# PT08.net
KiCad netlist of a schematic drawn in EAGLE
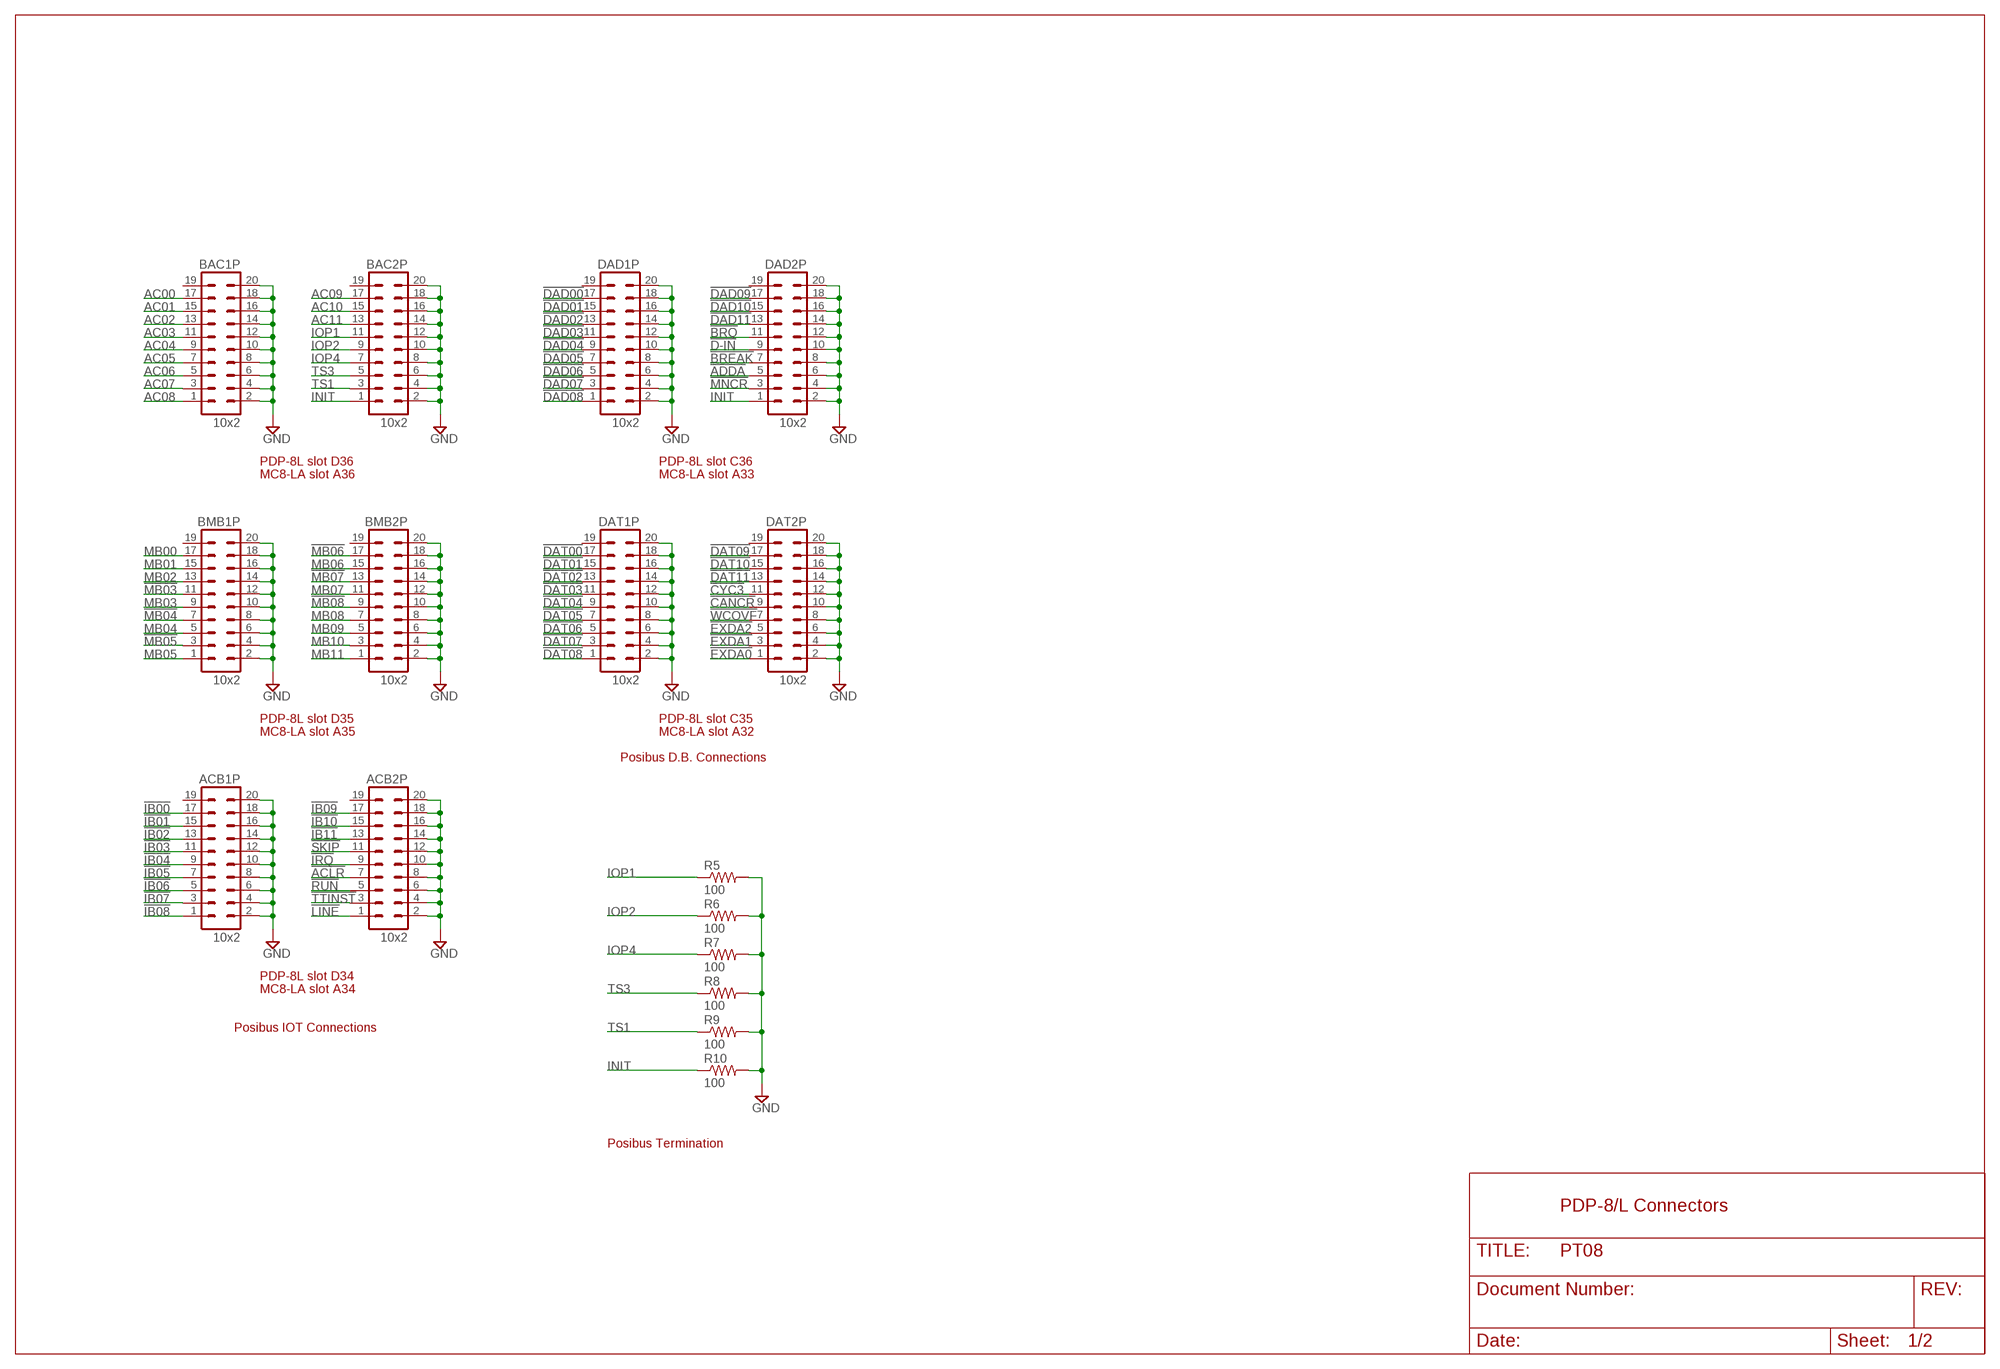
[diagram p0: schematic, sheet 1]
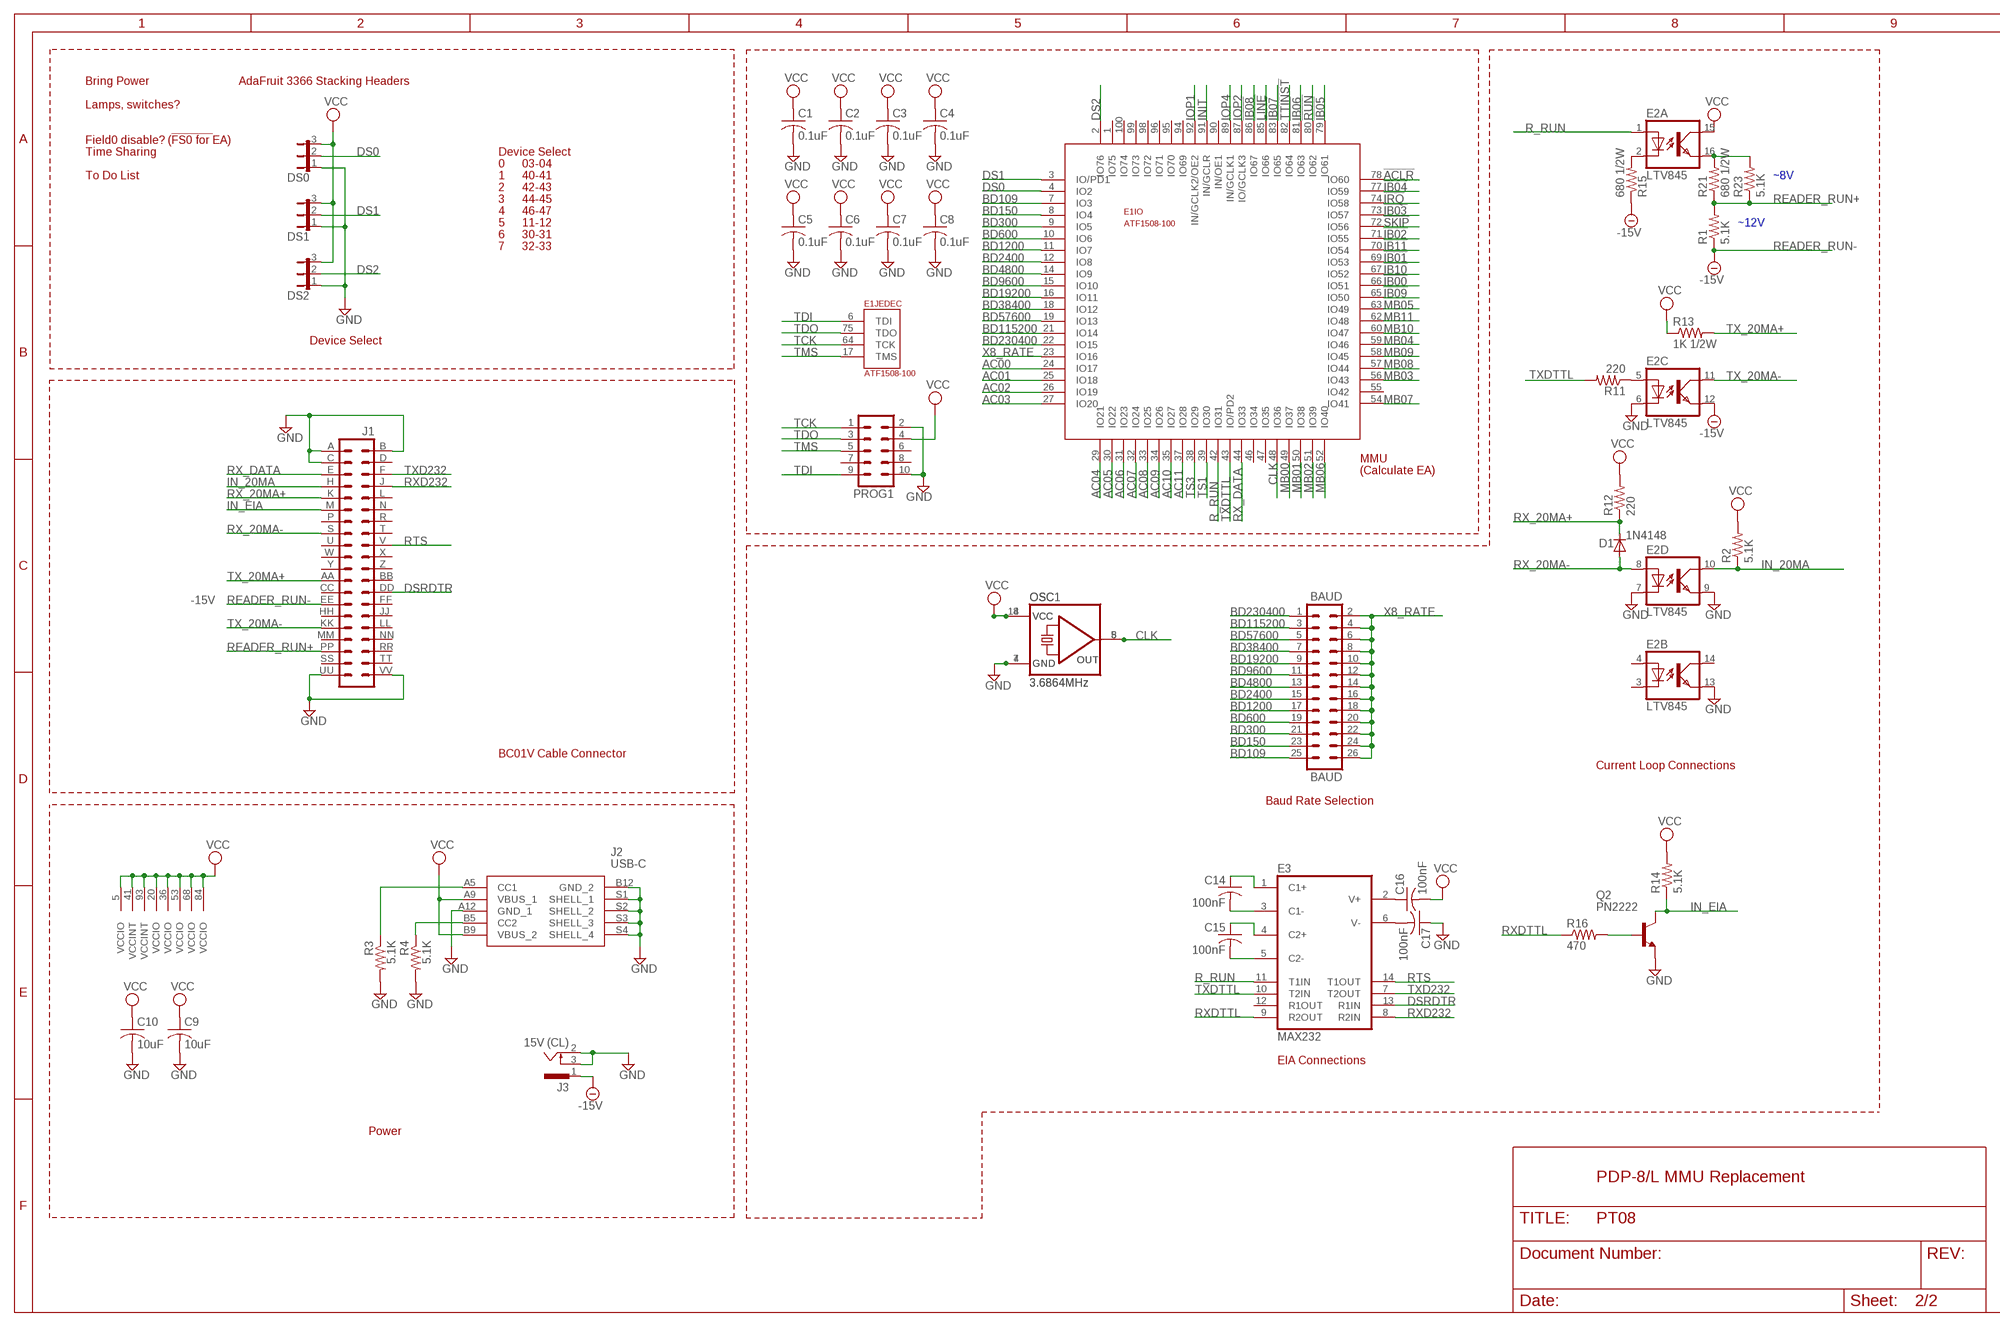
[diagram p1: schematic, sheet 2, part 1 of 2]
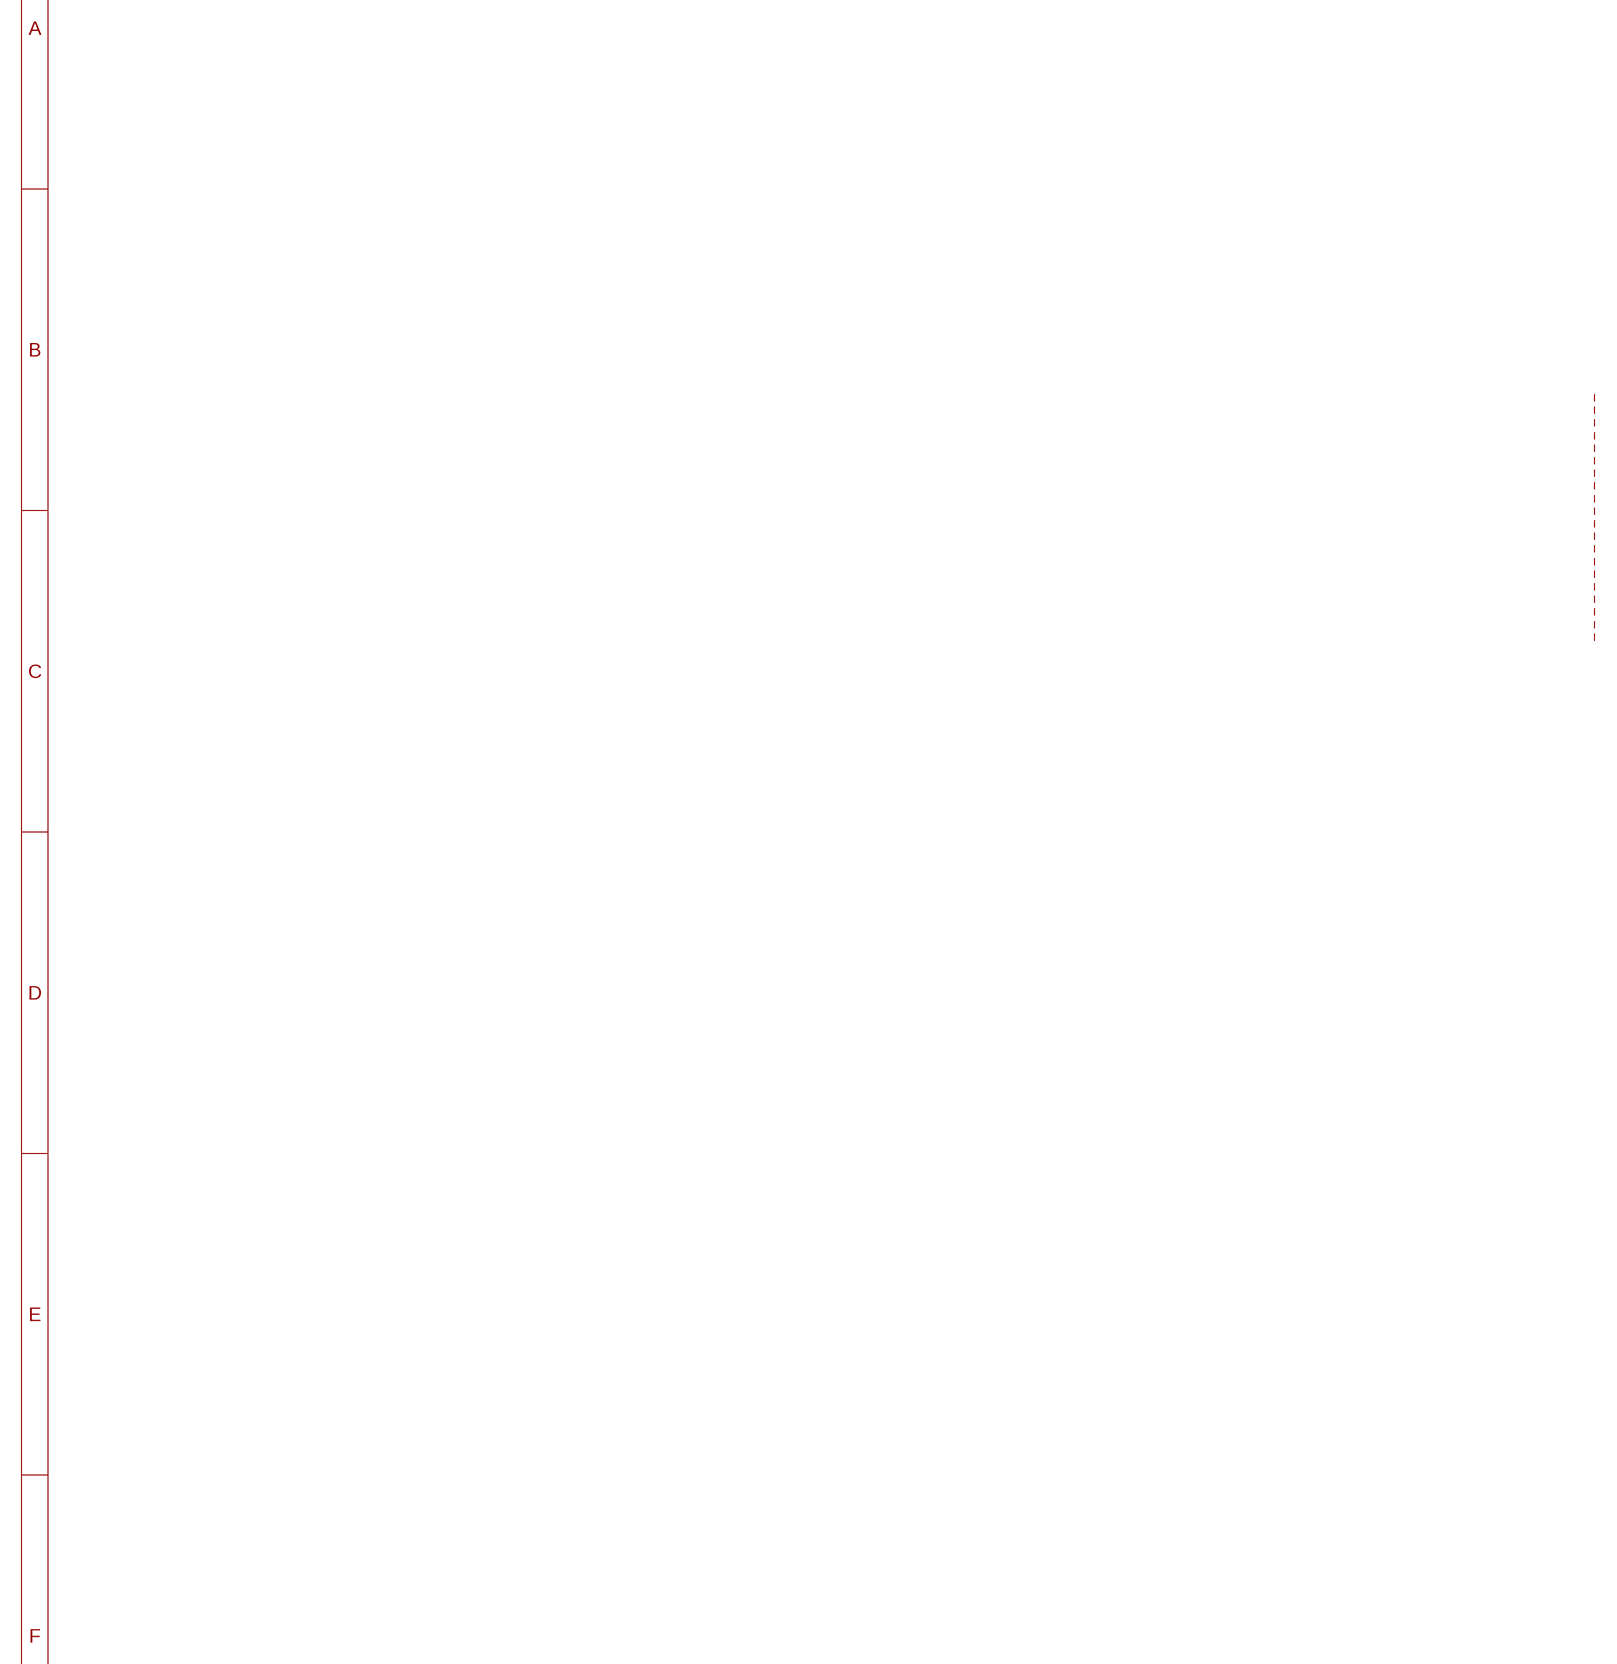
[diagram p2: schematic, sheet 2, part 2 of 2]

(export (version "E")
  (design (tool "Eeschema 10.0.6"))
  (components
    (comp (ref "BAUD")
      (value "BAUD")
      (footprint "eagle-import:MA13-2")
      (libsource (lib "eagle-import") (part "MA13-2"))
    )
    (comp (ref "C1")
      (value "0.1uF")
      (footprint "eagle-import:C0805")
      (libsource (lib "eagle-import") (part "C-USC0805"))
    )
    (comp (ref "C2")
      (value "0.1uF")
      (footprint "eagle-import:C0805")
      (libsource (lib "eagle-import") (part "C-USC0805"))
    )
    (comp (ref "C3")
      (value "0.1uF")
      (footprint "eagle-import:C0805")
      (libsource (lib "eagle-import") (part "C-USC0805"))
    )
    (comp (ref "C4")
      (value "0.1uF")
      (footprint "eagle-import:C0805")
      (libsource (lib "eagle-import") (part "C-USC0805"))
    )
    (comp (ref "C5")
      (value "0.1uF")
      (footprint "eagle-import:C0805")
      (libsource (lib "eagle-import") (part "C-USC0805"))
    )
    (comp (ref "C6")
      (value "0.1uF")
      (footprint "eagle-import:C0805")
      (libsource (lib "eagle-import") (part "C-USC0805"))
    )
    (comp (ref "C7")
      (value "0.1uF")
      (footprint "eagle-import:C0805")
      (libsource (lib "eagle-import") (part "C-USC0805"))
    )
    (comp (ref "C8")
      (value "0.1uF")
      (footprint "eagle-import:C0805")
      (libsource (lib "eagle-import") (part "C-USC0805"))
    )
    (comp (ref "C9")
      (value "10uF")
      (footprint "eagle-import:C0805")
      (libsource (lib "eagle-import") (part "C-USC0805"))
    )
    (comp (ref "C10")
      (value "10uF")
      (footprint "eagle-import:C0805")
      (libsource (lib "eagle-import") (part "C-USC0805"))
    )
    (comp (ref "C14")
      (value "100nF")
      (footprint "eagle-import:C0805")
      (libsource (lib "eagle-import") (part "C-USC0805"))
    )
    (comp (ref "C15")
      (value "100nF")
      (footprint "eagle-import:C0805")
      (libsource (lib "eagle-import") (part "C-USC0805"))
    )
    (comp (ref "C16")
      (value "100nF")
      (footprint "eagle-import:C0805")
      (libsource (lib "eagle-import") (part "C-USC0805"))
    )
    (comp (ref "C17")
      (value "100nF")
      (footprint "eagle-import:C0805")
      (libsource (lib "eagle-import") (part "C-USC0805"))
    )
    (comp (ref "D1")
      (value "1N4148")
      (footprint "eagle-import:SOD323-W")
      (libsource (lib "eagle-import") (part "DIODE-SOD323-W"))
    )
    (comp (ref "DS0")
      (value "JP2E")
      (footprint "eagle-import:JP2")
      (libsource (lib "eagle-import") (part "JP2E"))
    )
    (comp (ref "DS1")
      (value "JP2E")
      (footprint "eagle-import:JP2")
      (libsource (lib "eagle-import") (part "JP2E"))
    )
    (comp (ref "DS2")
      (value "JP2E")
      (footprint "eagle-import:JP2")
      (libsource (lib "eagle-import") (part "JP2E"))
    )
    (comp (ref "E1")
      (value "ATF1508-100")
      (footprint "eagle-import:PQFP-100")
      (libsource (lib "eagle-import") (part "ATF150X100PQFP"))
    )
    (comp (ref "E2")
      (value "LTV845")
      (footprint "eagle-import:DIL16")
      (fields (field (name "MF") "VISHAY/TELEFUNKEN") (field (name "MPN") "ILQ1"))
      (libsource (lib "eagle-import") (part "ILQ1"))
    )
    (comp (ref "E3")
      (value "MAX232")
      (footprint "eagle-import:DIL16")
      (fields (field (name "MF") "MAXIM") (field (name "MPN") "MAX232ACPE+"))
      (libsource (lib "eagle-import") (part "MAX232"))
    )
    (comp (ref "J1")
      (value "DEC40PINH")
      (footprint "eagle-import:DEC40PINH")
      (libsource (lib "eagle-import") (part "DEC40PINH"))
    )
    (comp (ref "J2")
      (value "USB-C")
      (footprint "eagle-import:USB497000A")
      (fields (field (name "MANUFACTURER_PART_NUMBER") "USB4970-00-A"))
      (libsource (lib "eagle-import") (part "USB4970-00-A"))
    )
    (comp (ref "J3")
      (value "15V (CL)")
      (footprint "eagle-import:SCD-014-A")
      (libsource (lib "eagle-import") (part "SCD-014A"))
    )
    (comp (ref "OSC")
      (value "3.6864MHz")
      (footprint "eagle-import:DIL08S")
      (libsource (lib "eagle-import") (part "QG5460"))
    )
    (comp (ref "OSC1")
      (value "3.6864MHz")
      (footprint "eagle-import:DIL14S")
      (libsource (lib "eagle-import") (part "QG5860"))
    )
    (comp (ref "PROG1")
      (value "ML10")
      (footprint "eagle-import:ML10")
      (libsource (lib "eagle-import") (part "ML10"))
    )
    (comp (ref "Q2")
      (value "PN2222")
      (footprint "eagle-import:SOT23-EBC")
      (libsource (lib "eagle-import") (part "-NPN-SOT23-EBC"))
    )
    (comp (ref "R1")
      (value "5.1K")
      (footprint "eagle-import:R0805")
      (libsource (lib "eagle-import") (part "R-US_R0805"))
    )
    (comp (ref "R2")
      (value "5.1K")
      (footprint "eagle-import:R0805")
      (libsource (lib "eagle-import") (part "R-US_R0805"))
    )
    (comp (ref "R3")
      (value "5.1K")
      (footprint "eagle-import:R0805")
      (libsource (lib "eagle-import") (part "R-US_R0805"))
    )
    (comp (ref "R4")
      (value "5.1K")
      (footprint "eagle-import:R0805")
      (libsource (lib "eagle-import") (part "R-US_R0805"))
    )
    (comp (ref "R11")
      (value "220")
      (footprint "eagle-import:R0805")
      (libsource (lib "eagle-import") (part "R-US_R0805"))
    )
    (comp (ref "R12")
      (value "220")
      (footprint "eagle-import:R0805")
      (libsource (lib "eagle-import") (part "R-US_R0805"))
    )
    (comp (ref "R13")
      (value "1K 1/2W")
      (footprint "eagle-import:0207_10")
      (libsource (lib "eagle-import") (part "R-US_0207/10"))
    )
    (comp (ref "R14")
      (value "5.1K")
      (footprint "eagle-import:R0805")
      (libsource (lib "eagle-import") (part "R-US_R0805"))
    )
    (comp (ref "R15")
      (value "680 1/2W")
      (footprint "eagle-import:0207_10")
      (libsource (lib "eagle-import") (part "R-US_0207/10"))
    )
    (comp (ref "R16")
      (value "470")
      (footprint "eagle-import:R0805")
      (libsource (lib "eagle-import") (part "R-US_R0805"))
    )
    (comp (ref "R21")
      (value "680 1/2W")
      (footprint "eagle-import:0207_10")
      (libsource (lib "eagle-import") (part "R-US_0207/10"))
    )
    (comp (ref "R23")
      (value "5.1K")
      (footprint "eagle-import:R0805")
      (libsource (lib "eagle-import") (part "R-US_R0805"))
    )
    (comp (ref "ACB1P")
      (value "10x2")
      (footprint "eagle-import:MA10-2")
      (libsource (lib "eagle-import") (part "MA10-2"))
    )
    (comp (ref "ACB2P")
      (value "10x2")
      (footprint "eagle-import:MA10-2")
      (libsource (lib "eagle-import") (part "MA10-2"))
    )
    (comp (ref "BAC1P")
      (value "10x2")
      (footprint "eagle-import:MA10-2")
      (libsource (lib "eagle-import") (part "MA10-2"))
    )
    (comp (ref "BAC2P")
      (value "10x2")
      (footprint "eagle-import:MA10-2")
      (libsource (lib "eagle-import") (part "MA10-2"))
    )
    (comp (ref "BMB1P")
      (value "10x2")
      (footprint "eagle-import:MA10-2")
      (libsource (lib "eagle-import") (part "MA10-2"))
    )
    (comp (ref "BMB2P")
      (value "10x2")
      (footprint "eagle-import:MA10-2")
      (libsource (lib "eagle-import") (part "MA10-2"))
    )
    (comp (ref "DAD1P")
      (value "10x2")
      (footprint "eagle-import:MA10-2")
      (libsource (lib "eagle-import") (part "MA10-2"))
    )
    (comp (ref "DAD2P")
      (value "10x2")
      (footprint "eagle-import:MA10-2")
      (libsource (lib "eagle-import") (part "MA10-2"))
    )
    (comp (ref "DAT1P")
      (value "10x2")
      (footprint "eagle-import:MA10-2")
      (libsource (lib "eagle-import") (part "MA10-2"))
    )
    (comp (ref "DAT2P")
      (value "10x2")
      (footprint "eagle-import:MA10-2")
      (libsource (lib "eagle-import") (part "MA10-2"))
    )
    (comp (ref "R5")
      (value "100")
      (footprint "eagle-import:R1206")
      (libsource (lib "eagle-import") (part "R-US_R1206"))
    )
    (comp (ref "R6")
      (value "100")
      (footprint "eagle-import:R1206")
      (libsource (lib "eagle-import") (part "R-US_R1206"))
    )
    (comp (ref "R7")
      (value "100")
      (footprint "eagle-import:R1206")
      (libsource (lib "eagle-import") (part "R-US_R1206"))
    )
    (comp (ref "R8")
      (value "100")
      (footprint "eagle-import:R1206")
      (libsource (lib "eagle-import") (part "R-US_R1206"))
    )
    (comp (ref "R9")
      (value "100")
      (footprint "eagle-import:R1206")
      (libsource (lib "eagle-import") (part "R-US_R1206"))
    )
    (comp (ref "R10")
      (value "100")
      (footprint "eagle-import:R1206")
      (libsource (lib "eagle-import") (part "R-US_R1206"))
    )
  )
  (nets
    (net (code "1") (name "-15V") (class "Default")
      (node (ref "E2") (pin "12") (pinfunction "EMIT_12") (pintype "passive"))
      (node (ref "J1") (pin "EE") (pinfunction "27_EE") (pintype "bidirectional"))
      (node (ref "J3") (pin "1") (pinfunction "1_1") (pintype "passive"))
      (node (ref "R1") (pin "1") (pinfunction "1_1") (pintype "passive"))
      (node (ref "R15") (pin "1") (pinfunction "1_1") (pintype "passive"))
    )
    (net (code "2") (name "AC00") (class "Default")
      (node (ref "BAC1P") (pin "17") (pinfunction "17_17") (pintype "passive"))
      (node (ref "E1") (pin "24") (pinfunction "IO17_24") (pintype "bidirectional"))
    )
    (net (code "3") (name "AC01") (class "Default")
      (node (ref "BAC1P") (pin "15") (pinfunction "15_15") (pintype "passive"))
      (node (ref "E1") (pin "25") (pinfunction "IO18_25") (pintype "bidirectional"))
    )
    (net (code "4") (name "AC02") (class "Default")
      (node (ref "BAC1P") (pin "13") (pinfunction "13_13") (pintype "passive"))
      (node (ref "E1") (pin "26") (pinfunction "IO19_26") (pintype "bidirectional"))
    )
    (net (code "5") (name "AC03") (class "Default")
      (node (ref "BAC1P") (pin "11") (pinfunction "11_11") (pintype "passive"))
      (node (ref "E1") (pin "27") (pinfunction "IO20_27") (pintype "bidirectional"))
    )
    (net (code "6") (name "AC04") (class "Default")
      (node (ref "BAC1P") (pin "9") (pinfunction "9_9") (pintype "passive"))
      (node (ref "E1") (pin "29") (pinfunction "IO21_29") (pintype "bidirectional"))
    )
    (net (code "7") (name "AC05") (class "Default")
      (node (ref "BAC1P") (pin "7") (pinfunction "7_7") (pintype "passive"))
      (node (ref "E1") (pin "30") (pinfunction "IO22_30") (pintype "bidirectional"))
    )
    (net (code "8") (name "AC06") (class "Default")
      (node (ref "BAC1P") (pin "5") (pinfunction "5_5") (pintype "passive"))
      (node (ref "E1") (pin "31") (pinfunction "IO23_31") (pintype "bidirectional"))
    )
    (net (code "9") (name "AC07") (class "Default")
      (node (ref "BAC1P") (pin "3") (pinfunction "3_3") (pintype "passive"))
      (node (ref "E1") (pin "32") (pinfunction "IO24_32") (pintype "bidirectional"))
    )
    (net (code "10") (name "AC08") (class "Default")
      (node (ref "BAC1P") (pin "1") (pinfunction "1_1") (pintype "passive"))
      (node (ref "E1") (pin "33") (pinfunction "IO25_33") (pintype "bidirectional"))
    )
    (net (code "11") (name "AC09") (class "Default")
      (node (ref "BAC2P") (pin "17") (pinfunction "17_17") (pintype "passive"))
      (node (ref "E1") (pin "34") (pinfunction "IO26_34") (pintype "bidirectional"))
    )
    (net (code "12") (name "AC10") (class "Default")
      (node (ref "BAC2P") (pin "15") (pinfunction "15_15") (pintype "passive"))
      (node (ref "E1") (pin "35") (pinfunction "IO27_35") (pintype "bidirectional"))
    )
    (net (code "13") (name "AC11") (class "Default")
      (node (ref "BAC2P") (pin "13") (pinfunction "13_13") (pintype "passive"))
      (node (ref "E1") (pin "37") (pinfunction "IO28_37") (pintype "bidirectional"))
    )
    (net (code "14") (name "BD109") (class "Default")
      (node (ref "BAUD") (pin "25") (pinfunction "25_25") (pintype "passive"))
      (node (ref "E1") (pin "7") (pinfunction "IO3_7") (pintype "bidirectional"))
    )
    (net (code "15") (name "BD150") (class "Default")
      (node (ref "BAUD") (pin "23") (pinfunction "23_23") (pintype "passive"))
      (node (ref "E1") (pin "8") (pinfunction "IO4_8") (pintype "bidirectional"))
    )
    (net (code "16") (name "BD300") (class "Default")
      (node (ref "BAUD") (pin "21") (pinfunction "21_21") (pintype "passive"))
      (node (ref "E1") (pin "9") (pinfunction "IO5_9") (pintype "bidirectional"))
    )
    (net (code "17") (name "BD600") (class "Default")
      (node (ref "BAUD") (pin "19") (pinfunction "19_19") (pintype "passive"))
      (node (ref "E1") (pin "10") (pinfunction "IO6_10") (pintype "bidirectional"))
    )
    (net (code "18") (name "BD1200") (class "Default")
      (node (ref "BAUD") (pin "17") (pinfunction "17_17") (pintype "passive"))
      (node (ref "E1") (pin "11") (pinfunction "IO7_11") (pintype "bidirectional"))
    )
    (net (code "19") (name "BD2400") (class "Default")
      (node (ref "BAUD") (pin "15") (pinfunction "15_15") (pintype "passive"))
      (node (ref "E1") (pin "12") (pinfunction "IO8_12") (pintype "bidirectional"))
    )
    (net (code "20") (name "BD4800") (class "Default")
      (node (ref "BAUD") (pin "13") (pinfunction "13_13") (pintype "passive"))
      (node (ref "E1") (pin "14") (pinfunction "IO9_14") (pintype "bidirectional"))
    )
    (net (code "21") (name "BD9600") (class "Default")
      (node (ref "BAUD") (pin "11") (pinfunction "11_11") (pintype "passive"))
      (node (ref "E1") (pin "15") (pinfunction "IO10_15") (pintype "bidirectional"))
    )
    (net (code "22") (name "BD19200") (class "Default")
      (node (ref "BAUD") (pin "9") (pinfunction "9_9") (pintype "passive"))
      (node (ref "E1") (pin "16") (pinfunction "IO11_16") (pintype "bidirectional"))
    )
    (net (code "23") (name "BD38400") (class "Default")
      (node (ref "BAUD") (pin "7") (pinfunction "7_7") (pintype "passive"))
      (node (ref "E1") (pin "18") (pinfunction "IO12_18") (pintype "bidirectional"))
    )
    (net (code "24") (name "BD57600") (class "Default")
      (node (ref "BAUD") (pin "5") (pinfunction "5_5") (pintype "passive"))
      (node (ref "E1") (pin "19") (pinfunction "IO13_19") (pintype "bidirectional"))
    )
    (net (code "25") (name "BD115200") (class "Default")
      (node (ref "BAUD") (pin "3") (pinfunction "3_3") (pintype "passive"))
      (node (ref "E1") (pin "21") (pinfunction "IO14_21") (pintype "bidirectional"))
    )
    (net (code "26") (name "BD230400") (class "Default")
      (node (ref "BAUD") (pin "1") (pinfunction "1_1") (pintype "passive"))
      (node (ref "E1") (pin "22") (pinfunction "IO15_22") (pintype "bidirectional"))
    )
    (net (code "27") (name "CLK") (class "Default")
      (node (ref "E1") (pin "48") (pinfunction "IO36_48") (pintype "bidirectional"))
      (node (ref "OSC") (pin "5") (pinfunction "OUT_5") (pintype "output"))
      (node (ref "OSC1") (pin "8") (pinfunction "OUT_8") (pintype "output"))
    )
    (net (code "28") (name "DS0") (class "Default")
      (node (ref "DS0") (pin "2") (pinfunction "2_2") (pintype "passive"))
      (node (ref "E1") (pin "4") (pinfunction "IO2_4") (pintype "bidirectional"))
    )
    (net (code "29") (name "DS1") (class "Default")
      (node (ref "DS1") (pin "2") (pinfunction "2_2") (pintype "passive"))
      (node (ref "E1") (pin "3") (pinfunction "IO/PD1_3") (pintype "bidirectional"))
    )
    (net (code "30") (name "DS2") (class "Default")
      (node (ref "DS2") (pin "2") (pinfunction "2_2") (pintype "passive"))
      (node (ref "E1") (pin "2") (pinfunction "IO76_2") (pintype "bidirectional"))
    )
    (net (code "31") (name "DSRDTR") (class "Default")
      (node (ref "E3") (pin "13") (pinfunction "R1IN_13") (pintype "input"))
      (node (ref "J1") (pin "DD") (pinfunction "26_DD") (pintype "bidirectional"))
    )
    (net (code "32") (name "GND") (class "Default")
      (node (ref "ACB1P") (pin "10") (pinfunction "10_10") (pintype "passive"))
      (node (ref "ACB1P") (pin "12") (pinfunction "12_12") (pintype "passive"))
      (node (ref "ACB1P") (pin "14") (pinfunction "14_14") (pintype "passive"))
      (node (ref "ACB1P") (pin "16") (pinfunction "16_16") (pintype "passive"))
      (node (ref "ACB1P") (pin "18") (pinfunction "18_18") (pintype "passive"))
      (node (ref "ACB1P") (pin "2") (pinfunction "2_2") (pintype "passive"))
      (node (ref "ACB1P") (pin "20") (pinfunction "20_20") (pintype "passive"))
      (node (ref "ACB1P") (pin "4") (pinfunction "4_4") (pintype "passive"))
      (node (ref "ACB1P") (pin "6") (pinfunction "6_6") (pintype "passive"))
      (node (ref "ACB1P") (pin "8") (pinfunction "8_8") (pintype "passive"))
      (node (ref "ACB2P") (pin "10") (pinfunction "10_10") (pintype "passive"))
      (node (ref "ACB2P") (pin "12") (pinfunction "12_12") (pintype "passive"))
      (node (ref "ACB2P") (pin "14") (pinfunction "14_14") (pintype "passive"))
      (node (ref "ACB2P") (pin "16") (pinfunction "16_16") (pintype "passive"))
      (node (ref "ACB2P") (pin "18") (pinfunction "18_18") (pintype "passive"))
      (node (ref "ACB2P") (pin "2") (pinfunction "2_2") (pintype "passive"))
      (node (ref "ACB2P") (pin "20") (pinfunction "20_20") (pintype "passive"))
      (node (ref "ACB2P") (pin "4") (pinfunction "4_4") (pintype "passive"))
      (node (ref "ACB2P") (pin "6") (pinfunction "6_6") (pintype "passive"))
      (node (ref "ACB2P") (pin "8") (pinfunction "8_8") (pintype "passive"))
      (node (ref "BAC1P") (pin "10") (pinfunction "10_10") (pintype "passive"))
      (node (ref "BAC1P") (pin "12") (pinfunction "12_12") (pintype "passive"))
      (node (ref "BAC1P") (pin "14") (pinfunction "14_14") (pintype "passive"))
      (node (ref "BAC1P") (pin "16") (pinfunction "16_16") (pintype "passive"))
      (node (ref "BAC1P") (pin "18") (pinfunction "18_18") (pintype "passive"))
      (node (ref "BAC1P") (pin "2") (pinfunction "2_2") (pintype "passive"))
      (node (ref "BAC1P") (pin "20") (pinfunction "20_20") (pintype "passive"))
      (node (ref "BAC1P") (pin "4") (pinfunction "4_4") (pintype "passive"))
      (node (ref "BAC1P") (pin "6") (pinfunction "6_6") (pintype "passive"))
      (node (ref "BAC1P") (pin "8") (pinfunction "8_8") (pintype "passive"))
      (node (ref "BAC2P") (pin "10") (pinfunction "10_10") (pintype "passive"))
      (node (ref "BAC2P") (pin "12") (pinfunction "12_12") (pintype "passive"))
      (node (ref "BAC2P") (pin "14") (pinfunction "14_14") (pintype "passive"))
      (node (ref "BAC2P") (pin "16") (pinfunction "16_16") (pintype "passive"))
      (node (ref "BAC2P") (pin "18") (pinfunction "18_18") (pintype "passive"))
      (node (ref "BAC2P") (pin "2") (pinfunction "2_2") (pintype "passive"))
      (node (ref "BAC2P") (pin "20") (pinfunction "20_20") (pintype "passive"))
      (node (ref "BAC2P") (pin "4") (pinfunction "4_4") (pintype "passive"))
      (node (ref "BAC2P") (pin "6") (pinfunction "6_6") (pintype "passive"))
      (node (ref "BAC2P") (pin "8") (pinfunction "8_8") (pintype "passive"))
      (node (ref "BMB1P") (pin "10") (pinfunction "10_10") (pintype "passive"))
      (node (ref "BMB1P") (pin "12") (pinfunction "12_12") (pintype "passive"))
      (node (ref "BMB1P") (pin "14") (pinfunction "14_14") (pintype "passive"))
      (node (ref "BMB1P") (pin "16") (pinfunction "16_16") (pintype "passive"))
      (node (ref "BMB1P") (pin "18") (pinfunction "18_18") (pintype "passive"))
      (node (ref "BMB1P") (pin "2") (pinfunction "2_2") (pintype "passive"))
      (node (ref "BMB1P") (pin "20") (pinfunction "20_20") (pintype "passive"))
      (node (ref "BMB1P") (pin "4") (pinfunction "4_4") (pintype "passive"))
      (node (ref "BMB1P") (pin "6") (pinfunction "6_6") (pintype "passive"))
      (node (ref "BMB1P") (pin "8") (pinfunction "8_8") (pintype "passive"))
      (node (ref "BMB2P") (pin "10") (pinfunction "10_10") (pintype "passive"))
      (node (ref "BMB2P") (pin "12") (pinfunction "12_12") (pintype "passive"))
      (node (ref "BMB2P") (pin "14") (pinfunction "14_14") (pintype "passive"))
      (node (ref "BMB2P") (pin "16") (pinfunction "16_16") (pintype "passive"))
      (node (ref "BMB2P") (pin "18") (pinfunction "18_18") (pintype "passive"))
      (node (ref "BMB2P") (pin "2") (pinfunction "2_2") (pintype "passive"))
      (node (ref "BMB2P") (pin "20") (pinfunction "20_20") (pintype "passive"))
      (node (ref "BMB2P") (pin "4") (pinfunction "4_4") (pintype "passive"))
      (node (ref "BMB2P") (pin "6") (pinfunction "6_6") (pintype "passive"))
      (node (ref "BMB2P") (pin "8") (pinfunction "8_8") (pintype "passive"))
      (node (ref "C1") (pin "2") (pinfunction "2_2") (pintype "passive"))
      (node (ref "C10") (pin "2") (pinfunction "2_2") (pintype "passive"))
      (node (ref "C17") (pin "1") (pinfunction "1_1") (pintype "passive"))
      (node (ref "C2") (pin "2") (pinfunction "2_2") (pintype "passive"))
      (node (ref "C3") (pin "2") (pinfunction "2_2") (pintype "passive"))
      (node (ref "C4") (pin "2") (pinfunction "2_2") (pintype "passive"))
      (node (ref "C5") (pin "2") (pinfunction "2_2") (pintype "passive"))
      (node (ref "C6") (pin "2") (pinfunction "2_2") (pintype "passive"))
      (node (ref "C7") (pin "2") (pinfunction "2_2") (pintype "passive"))
      (node (ref "C8") (pin "2") (pinfunction "2_2") (pintype "passive"))
      (node (ref "C9") (pin "2") (pinfunction "2_2") (pintype "passive"))
      (node (ref "DAD1P") (pin "10") (pinfunction "10_10") (pintype "passive"))
      (node (ref "DAD1P") (pin "12") (pinfunction "12_12") (pintype "passive"))
      (node (ref "DAD1P") (pin "14") (pinfunction "14_14") (pintype "passive"))
      (node (ref "DAD1P") (pin "16") (pinfunction "16_16") (pintype "passive"))
      (node (ref "DAD1P") (pin "18") (pinfunction "18_18") (pintype "passive"))
      (node (ref "DAD1P") (pin "2") (pinfunction "2_2") (pintype "passive"))
      (node (ref "DAD1P") (pin "20") (pinfunction "20_20") (pintype "passive"))
      (node (ref "DAD1P") (pin "4") (pinfunction "4_4") (pintype "passive"))
      (node (ref "DAD1P") (pin "6") (pinfunction "6_6") (pintype "passive"))
      (node (ref "DAD1P") (pin "8") (pinfunction "8_8") (pintype "passive"))
      (node (ref "DAD2P") (pin "10") (pinfunction "10_10") (pintype "passive"))
      (node (ref "DAD2P") (pin "12") (pinfunction "12_12") (pintype "passive"))
      (node (ref "DAD2P") (pin "14") (pinfunction "14_14") (pintype "passive"))
      (node (ref "DAD2P") (pin "16") (pinfunction "16_16") (pintype "passive"))
      (node (ref "DAD2P") (pin "18") (pinfunction "18_18") (pintype "passive"))
      (node (ref "DAD2P") (pin "2") (pinfunction "2_2") (pintype "passive"))
      (node (ref "DAD2P") (pin "20") (pinfunction "20_20") (pintype "passive"))
      (node (ref "DAD2P") (pin "4") (pinfunction "4_4") (pintype "passive"))
      (node (ref "DAD2P") (pin "6") (pinfunction "6_6") (pintype "passive"))
      (node (ref "DAD2P") (pin "8") (pinfunction "8_8") (pintype "passive"))
      (node (ref "DAT1P") (pin "10") (pinfunction "10_10") (pintype "passive"))
      (node (ref "DAT1P") (pin "12") (pinfunction "12_12") (pintype "passive"))
      (node (ref "DAT1P") (pin "14") (pinfunction "14_14") (pintype "passive"))
      (node (ref "DAT1P") (pin "16") (pinfunction "16_16") (pintype "passive"))
      (node (ref "DAT1P") (pin "18") (pinfunction "18_18") (pintype "passive"))
      (node (ref "DAT1P") (pin "2") (pinfunction "2_2") (pintype "passive"))
      (node (ref "DAT1P") (pin "20") (pinfunction "20_20") (pintype "passive"))
      (node (ref "DAT1P") (pin "4") (pinfunction "4_4") (pintype "passive"))
      (node (ref "DAT1P") (pin "6") (pinfunction "6_6") (pintype "passive"))
      (node (ref "DAT1P") (pin "8") (pinfunction "8_8") (pintype "passive"))
      (node (ref "DAT2P") (pin "10") (pinfunction "10_10") (pintype "passive"))
      (node (ref "DAT2P") (pin "12") (pinfunction "12_12") (pintype "passive"))
      (node (ref "DAT2P") (pin "14") (pinfunction "14_14") (pintype "passive"))
      (node (ref "DAT2P") (pin "16") (pinfunction "16_16") (pintype "passive"))
      (node (ref "DAT2P") (pin "18") (pinfunction "18_18") (pintype "passive"))
      (node (ref "DAT2P") (pin "2") (pinfunction "2_2") (pintype "passive"))
      (node (ref "DAT2P") (pin "20") (pinfunction "20_20") (pintype "passive"))
      (node (ref "DAT2P") (pin "4") (pinfunction "4_4") (pintype "passive"))
      (node (ref "DAT2P") (pin "6") (pinfunction "6_6") (pintype "passive"))
      (node (ref "DAT2P") (pin "8") (pinfunction "8_8") (pintype "passive"))
      (node (ref "DS0") (pin "1") (pinfunction "1_1") (pintype "passive"))
      (node (ref "DS1") (pin "1") (pinfunction "1_1") (pintype "passive"))
      (node (ref "DS2") (pin "1") (pinfunction "1_1") (pintype "passive"))
      (node (ref "E2") (pin "13") (pinfunction "EMIT_13") (pintype "passive"))
      (node (ref "E2") (pin "6") (pinfunction "C_6") (pintype "passive"))
      (node (ref "E2") (pin "7") (pinfunction "C_7") (pintype "passive"))
      (node (ref "E2") (pin "9") (pinfunction "EMIT_9") (pintype "passive"))
      (node (ref "J1") (pin "A") (pinfunction "1_A") (pintype "bidirectional"))
      (node (ref "J1") (pin "B") (pinfunction "2_B") (pintype "bidirectional"))
      (node (ref "J1") (pin "C") (pinfunction "3_C") (pintype "bidirectional"))
      (node (ref "J1") (pin "UU") (pinfunction "39_UU") (pintype "bidirectional"))
      (node (ref "J1") (pin "VV") (pinfunction "40_VV") (pintype "bidirectional"))
      (node (ref "J2") (pin "A12") (pinfunction "GND_1_A12") (pintype "bidirectional"))
      (node (ref "J2") (pin "B12") (pinfunction "GND_2_B12") (pintype "bidirectional"))
      (node (ref "J2") (pin "S1") (pinfunction "SHELL_1_S1") (pintype "bidirectional"))
      (node (ref "J2") (pin "S2") (pinfunction "SHELL_2_S2") (pintype "bidirectional"))
      (node (ref "J2") (pin "S3") (pinfunction "SHELL_3_S3") (pintype "bidirectional"))
      (node (ref "J2") (pin "S4") (pinfunction "SHELL_4_S4") (pintype "bidirectional"))
      (node (ref "J3") (pin "2") (pinfunction "2_2") (pintype "passive"))
      (node (ref "J3") (pin "3") (pinfunction "3_3") (pintype "passive"))
      (node (ref "OSC") (pin "4") (pinfunction "GND_4") (pintype "power_in"))
      (node (ref "OSC1") (pin "7") (pinfunction "GND_7") (pintype "power_in"))
      (node (ref "PROG1") (pin "10") (pinfunction "10_10") (pintype "passive"))
      (node (ref "PROG1") (pin "2") (pinfunction "2_2") (pintype "passive"))
      (node (ref "Q2") (pin "E") (pinfunction "E_E") (pintype "passive"))
      (node (ref "R10") (pin "2") (pinfunction "2_2") (pintype "passive"))
      (node (ref "R3") (pin "2") (pinfunction "2_2") (pintype "passive"))
      (node (ref "R4") (pin "2") (pinfunction "2_2") (pintype "passive"))
      (node (ref "R5") (pin "2") (pinfunction "2_2") (pintype "passive"))
      (node (ref "R6") (pin "2") (pinfunction "2_2") (pintype "passive"))
      (node (ref "R7") (pin "2") (pinfunction "2_2") (pintype "passive"))
      (node (ref "R8") (pin "2") (pinfunction "2_2") (pintype "passive"))
      (node (ref "R9") (pin "2") (pinfunction "2_2") (pintype "passive"))
    )
    (net (code "33") (name "INIT") (class "Default")
      (node (ref "BAC2P") (pin "1") (pinfunction "1_1") (pintype "passive"))
      (node (ref "DAD2P") (pin "1") (pinfunction "1_1") (pintype "passive"))
      (node (ref "E1") (pin "91") (pinfunction "IN/GCLR_91") (pintype "input"))
      (node (ref "R10") (pin "1") (pinfunction "1_1") (pintype "passive"))
    )
    (net (code "34") (name "IN_20MA") (class "Default")
      (node (ref "E2") (pin "10") (pinfunction "COL_10") (pintype "passive"))
      (node (ref "J1") (pin "H") (pinfunction "7_H") (pintype "bidirectional"))
      (node (ref "R2") (pin "1") (pinfunction "1_1") (pintype "passive"))
    )
    (net (code "35") (name "IN_EIA") (class "Default")
      (node (ref "J1") (pin "M") (pinfunction "11_M") (pintype "bidirectional"))
      (node (ref "Q2") (pin "C") (pinfunction "C_C") (pintype "passive"))
      (node (ref "R14") (pin "1") (pinfunction "1_1") (pintype "passive"))
    )
    (net (code "36") (name "IOP1") (class "Default")
      (node (ref "BAC2P") (pin "11") (pinfunction "11_11") (pintype "passive"))
      (node (ref "E1") (pin "92") (pinfunction "IN/GCLK2/OE2_92") (pintype "input"))
      (node (ref "R5") (pin "1") (pinfunction "1_1") (pintype "passive"))
    )
    (net (code "37") (name "IOP2") (class "Default")
      (node (ref "BAC2P") (pin "9") (pinfunction "9_9") (pintype "passive"))
      (node (ref "E1") (pin "87") (pinfunction "IO/GCLK3_87") (pintype "bidirectional"))
      (node (ref "R6") (pin "1") (pinfunction "1_1") (pintype "passive"))
    )
    (net (code "38") (name "IOP4") (class "Default")
      (node (ref "BAC2P") (pin "7") (pinfunction "7_7") (pintype "passive"))
      (node (ref "E1") (pin "89") (pinfunction "IN/GCLK1_89") (pintype "input"))
      (node (ref "R7") (pin "1") (pinfunction "1_1") (pintype "passive"))
    )
    (net (code "39") (name "MB00") (class "Default")
      (node (ref "BMB1P") (pin "17") (pinfunction "17_17") (pintype "passive"))
      (node (ref "E1") (pin "49") (pinfunction "IO37_49") (pintype "bidirectional"))
    )
    (net (code "40") (name "MB01") (class "Default")
      (node (ref "BMB1P") (pin "15") (pinfunction "15_15") (pintype "passive"))
      (node (ref "E1") (pin "50") (pinfunction "IO38_50") (pintype "bidirectional"))
    )
    (net (code "41") (name "MB02") (class "Default")
      (node (ref "BMB1P") (pin "13") (pinfunction "13_13") (pintype "passive"))
      (node (ref "E1") (pin "51") (pinfunction "IO39_51") (pintype "bidirectional"))
    )
    (net (code "42") (name "MB03") (class "Default")
      (node (ref "BMB1P") (pin "9") (pinfunction "9_9") (pintype "passive"))
      (node (ref "E1") (pin "56") (pinfunction "IO43_56") (pintype "bidirectional"))
    )
    (net (code "43") (name "MB04") (class "Default")
      (node (ref "BMB1P") (pin "5") (pinfunction "5_5") (pintype "passive"))
      (node (ref "E1") (pin "59") (pinfunction "IO46_59") (pintype "bidirectional"))
    )
    (net (code "44") (name "MB05") (class "Default")
      (node (ref "BMB1P") (pin "1") (pinfunction "1_1") (pintype "passive"))
      (node (ref "E1") (pin "63") (pinfunction "IO49_63") (pintype "bidirectional"))
    )
    (net (code "45") (name "MB06") (class "Default")
      (node (ref "BMB2P") (pin "15") (pinfunction "15_15") (pintype "passive"))
      (node (ref "E1") (pin "52") (pinfunction "IO40_52") (pintype "bidirectional"))
    )
    (net (code "46") (name "MB07") (class "Default")
      (node (ref "BMB2P") (pin "11") (pinfunction "11_11") (pintype "passive"))
      (node (ref "E1") (pin "54") (pinfunction "IO41_54") (pintype "bidirectional"))
    )
    (net (code "47") (name "MB08") (class "Default")
      (node (ref "BMB2P") (pin "7") (pinfunction "7_7") (pintype "passive"))
      (node (ref "E1") (pin "57") (pinfunction "IO44_57") (pintype "bidirectional"))
    )
    (net (code "48") (name "MB09") (class "Default")
      (node (ref "BMB2P") (pin "5") (pinfunction "5_5") (pintype "passive"))
      (node (ref "E1") (pin "58") (pinfunction "IO45_58") (pintype "bidirectional"))
    )
    (net (code "49") (name "MB10") (class "Default")
      (node (ref "BMB2P") (pin "3") (pinfunction "3_3") (pintype "passive"))
      (node (ref "E1") (pin "60") (pinfunction "IO47_60") (pintype "bidirectional"))
    )
    (net (code "50") (name "MB11") (class "Default")
      (node (ref "BMB2P") (pin "1") (pinfunction "1_1") (pintype "passive"))
      (node (ref "E1") (pin "62") (pinfunction "IO48_62") (pintype "bidirectional"))
    )
    (net (code "51") (name "Net-(E2A-C)") (class "Default")
      (node (ref "E2") (pin "2") (pinfunction "C_2") (pintype "passive"))
      (node (ref "R15") (pin "2") (pinfunction "2_2") (pintype "passive"))
    )
    (net (code "52") (name "Net-(E2A-EMIT)") (class "Default")
      (node (ref "E2") (pin "16") (pinfunction "EMIT_16") (pintype "passive"))
      (node (ref "R21") (pin "2") (pinfunction "2_2") (pintype "passive"))
      (node (ref "R23") (pin "2") (pinfunction "2_2") (pintype "passive"))
    )
    (net (code "53") (name "Net-(E2C-A)") (class "Default")
      (node (ref "E2") (pin "5") (pinfunction "A_5") (pintype "passive"))
      (node (ref "R11") (pin "1") (pinfunction "1_1") (pintype "passive"))
    )
    (net (code "54") (name "Net-(E3A-C1+)") (class "Default")
      (node (ref "C14") (pin "1") (pinfunction "1_1") (pintype "passive"))
      (node (ref "E3") (pin "1") (pinfunction "C1+_1") (pintype "bidirectional"))
    )
    (net (code "55") (name "Net-(E3A-C1-)") (class "Default")
      (node (ref "C14") (pin "2") (pinfunction "2_2") (pintype "passive"))
      (node (ref "E3") (pin "3") (pinfunction "C1-_3") (pintype "bidirectional"))
    )
    (net (code "56") (name "Net-(E3A-C2+)") (class "Default")
      (node (ref "C15") (pin "1") (pinfunction "1_1") (pintype "passive"))
      (node (ref "E3") (pin "4") (pinfunction "C2+_4") (pintype "bidirectional"))
    )
    (net (code "57") (name "Net-(E3A-C2-)") (class "Default")
      (node (ref "C15") (pin "2") (pinfunction "2_2") (pintype "passive"))
      (node (ref "E3") (pin "5") (pinfunction "C2-_5") (pintype "bidirectional"))
    )
    (net (code "58") (name "Net-(E3A-V+)") (class "Default")
      (node (ref "C16") (pin "1") (pinfunction "1_1") (pintype "passive"))
      (node (ref "E3") (pin "2") (pinfunction "V+_2") (pintype "bidirectional"))
    )
    (net (code "59") (name "Net-(E3A-V-)") (class "Default")
      (node (ref "C17") (pin "2") (pinfunction "2_2") (pintype "passive"))
      (node (ref "E3") (pin "6") (pinfunction "V-_6") (pintype "bidirectional"))
    )
    (net (code "60") (name "Net-(J2-CC1)") (class "Default")
      (node (ref "J2") (pin "A5") (pinfunction "CC1_A5") (pintype "bidirectional"))
      (node (ref "R3") (pin "1") (pinfunction "1_1") (pintype "passive"))
    )
    (net (code "61") (name "Net-(J2-CC2)") (class "Default")
      (node (ref "J2") (pin "B5") (pinfunction "CC2_B5") (pintype "bidirectional"))
      (node (ref "R4") (pin "1") (pinfunction "1_1") (pintype "passive"))
    )
    (net (code "62") (name "Net-(Q2-PadB)") (class "Default")
      (node (ref "Q2") (pin "B") (pinfunction "B_B") (pintype "passive"))
      (node (ref "R16") (pin "2") (pinfunction "2_2") (pintype "passive"))
    )
    (net (code "63") (name "READER_RUN+") (class "Default")
      (node (ref "J1") (pin "PP") (pinfunction "35_PP") (pintype "bidirectional"))
      (node (ref "R1") (pin "2") (pinfunction "2_2") (pintype "passive"))
      (node (ref "R21") (pin "1") (pinfunction "1_1") (pintype "passive"))
      (node (ref "R23") (pin "1") (pinfunction "1_1") (pintype "passive"))
    )
    (net (code "64") (name "RTS") (class "Default")
      (node (ref "E3") (pin "14") (pinfunction "T1OUT_14") (pintype "output"))
      (node (ref "J1") (pin "V") (pinfunction "18_V") (pintype "bidirectional"))
    )
    (net (code "65") (name "RXD232") (class "Default")
      (node (ref "E3") (pin "8") (pinfunction "R2IN_8") (pintype "input"))
      (node (ref "J1") (pin "J") (pinfunction "8_J") (pintype "bidirectional"))
    )
    (net (code "66") (name "RXDTTL") (class "Default")
      (node (ref "E3") (pin "9") (pinfunction "R2OUT_9") (pintype "output"))
      (node (ref "R16") (pin "1") (pinfunction "1_1") (pintype "passive"))
    )
    (net (code "67") (name "RX_20MA+") (class "Default")
      (node (ref "D1") (pin "C") (pinfunction "C_C") (pintype "passive"))
      (node (ref "J1") (pin "K") (pinfunction "9_K") (pintype "bidirectional"))
      (node (ref "R12") (pin "1") (pinfunction "1_1") (pintype "passive"))
    )
    (net (code "68") (name "RX_20MA-") (class "Default")
      (node (ref "D1") (pin "A") (pinfunction "A_A") (pintype "passive"))
      (node (ref "E2") (pin "8") (pinfunction "A_8") (pintype "passive"))
      (node (ref "J1") (pin "S") (pinfunction "15_S") (pintype "bidirectional"))
    )
    (net (code "69") (name "RX_DATA") (class "Default")
      (node (ref "E1") (pin "44") (pinfunction "IO33_44") (pintype "bidirectional"))
      (node (ref "J1") (pin "E") (pinfunction "5_E") (pintype "bidirectional"))
    )
    (net (code "70") (name "R_RUN") (class "Default")
      (node (ref "E1") (pin "42") (pinfunction "IO31_42") (pintype "bidirectional"))
      (node (ref "E2") (pin "1") (pinfunction "A_1") (pintype "passive"))
      (node (ref "E3") (pin "11") (pinfunction "T1IN_11") (pintype "input"))
    )
    (net (code "71") (name "TCK") (class "Default")
      (node (ref "E1") (pin "64") (pinfunction "TCK_64") (pintype "bidirectional"))
      (node (ref "PROG1") (pin "1") (pinfunction "1_1") (pintype "passive"))
    )
    (net (code "72") (name "TDI") (class "Default")
      (node (ref "E1") (pin "6") (pinfunction "TDI_6") (pintype "bidirectional"))
      (node (ref "PROG1") (pin "9") (pinfunction "9_9") (pintype "passive"))
    )
    (net (code "73") (name "TDO") (class "Default")
      (node (ref "E1") (pin "75") (pinfunction "TDO_75") (pintype "bidirectional"))
      (node (ref "PROG1") (pin "3") (pinfunction "3_3") (pintype "passive"))
    )
    (net (code "74") (name "TMS") (class "Default")
      (node (ref "E1") (pin "17") (pinfunction "TMS_17") (pintype "bidirectional"))
      (node (ref "PROG1") (pin "5") (pinfunction "5_5") (pintype "passive"))
    )
    (net (code "75") (name "TS1") (class "Default")
      (node (ref "BAC2P") (pin "3") (pinfunction "3_3") (pintype "passive"))
      (node (ref "E1") (pin "39") (pinfunction "IO30_39") (pintype "bidirectional"))
      (node (ref "R9") (pin "1") (pinfunction "1_1") (pintype "passive"))
    )
    (net (code "76") (name "TS3") (class "Default")
      (node (ref "BAC2P") (pin "5") (pinfunction "5_5") (pintype "passive"))
      (node (ref "E1") (pin "38") (pinfunction "IO29_38") (pintype "bidirectional"))
      (node (ref "R8") (pin "1") (pinfunction "1_1") (pintype "passive"))
    )
    (net (code "77") (name "TXD232") (class "Default")
      (node (ref "E3") (pin "7") (pinfunction "T2OUT_7") (pintype "output"))
      (node (ref "J1") (pin "F") (pinfunction "6_F") (pintype "bidirectional"))
    )
    (net (code "78") (name "TXDTTL") (class "Default")
      (node (ref "E1") (pin "43") (pinfunction "IO/PD2_43") (pintype "bidirectional"))
      (node (ref "E3") (pin "10") (pinfunction "T2IN_10") (pintype "input"))
      (node (ref "R11") (pin "2") (pinfunction "2_2") (pintype "passive"))
    )
    (net (code "79") (name "TX_20MA+") (class "Default")
      (node (ref "J1") (pin "AA") (pinfunction "23_AA") (pintype "bidirectional"))
      (node (ref "R13") (pin "2") (pinfunction "2_2") (pintype "passive"))
    )
    (net (code "80") (name "TX_20MA-") (class "Default")
      (node (ref "E2") (pin "11") (pinfunction "COL_11") (pintype "passive"))
      (node (ref "J1") (pin "KK") (pinfunction "31_KK") (pintype "bidirectional"))
    )
    (net (code "81") (name "VCC") (class "Default")
      (node (ref "C1") (pin "1") (pinfunction "1_1") (pintype "passive"))
      (node (ref "C10") (pin "1") (pinfunction "1_1") (pintype "passive"))
      (node (ref "C16") (pin "2") (pinfunction "2_2") (pintype "passive"))
      (node (ref "C2") (pin "1") (pinfunction "1_1") (pintype "passive"))
      (node (ref "C3") (pin "1") (pinfunction "1_1") (pintype "passive"))
      (node (ref "C4") (pin "1") (pinfunction "1_1") (pintype "passive"))
      (node (ref "C5") (pin "1") (pinfunction "1_1") (pintype "passive"))
      (node (ref "C6") (pin "1") (pinfunction "1_1") (pintype "passive"))
      (node (ref "C7") (pin "1") (pinfunction "1_1") (pintype "passive"))
      (node (ref "C8") (pin "1") (pinfunction "1_1") (pintype "passive"))
      (node (ref "C9") (pin "1") (pinfunction "1_1") (pintype "passive"))
      (node (ref "DS0") (pin "3") (pinfunction "3_3") (pintype "passive"))
      (node (ref "DS1") (pin "3") (pinfunction "3_3") (pintype "passive"))
      (node (ref "DS2") (pin "3") (pinfunction "3_3") (pintype "passive"))
      (node (ref "E1") (pin "20") (pinfunction "VCCIO_20") (pintype "power_in"))
      (node (ref "E1") (pin "36") (pinfunction "VCCIO_36") (pintype "power_in"))
      (node (ref "E1") (pin "41") (pinfunction "VCCINT_41") (pintype "power_in"))
      (node (ref "E1") (pin "5") (pinfunction "VCCIO_5") (pintype "power_in"))
      (node (ref "E1") (pin "53") (pinfunction "VCCIO_53") (pintype "power_in"))
      (node (ref "E1") (pin "68") (pinfunction "VCCIO_68") (pintype "power_in"))
      (node (ref "E1") (pin "84") (pinfunction "VCCIO_84") (pintype "power_in"))
      (node (ref "E1") (pin "93") (pinfunction "VCCINT_93") (pintype "power_in"))
      (node (ref "E2") (pin "15") (pinfunction "COL_15") (pintype "passive"))
      (node (ref "J2") (pin "A9") (pinfunction "VBUS_1_A9") (pintype "bidirectional"))
      (node (ref "J2") (pin "B9") (pinfunction "VBUS_2_B9") (pintype "bidirectional"))
      (node (ref "OSC") (pin "8") (pinfunction "VCC_8") (pintype "power_in"))
      (node (ref "OSC1") (pin "14") (pinfunction "VCC_14") (pintype "power_in"))
      (node (ref "PROG1") (pin "4") (pinfunction "4_4") (pintype "passive"))
      (node (ref "R12") (pin "2") (pinfunction "2_2") (pintype "passive"))
      (node (ref "R13") (pin "1") (pinfunction "1_1") (pintype "passive"))
      (node (ref "R14") (pin "2") (pinfunction "2_2") (pintype "passive"))
      (node (ref "R2") (pin "2") (pinfunction "2_2") (pintype "passive"))
    )
    (net (code "82") (name "X8_RATE") (class "Default")
      (node (ref "BAUD") (pin "10") (pinfunction "10_10") (pintype "passive"))
      (node (ref "BAUD") (pin "12") (pinfunction "12_12") (pintype "passive"))
      (node (ref "BAUD") (pin "14") (pinfunction "14_14") (pintype "passive"))
      (node (ref "BAUD") (pin "16") (pinfunction "16_16") (pintype "passive"))
      (node (ref "BAUD") (pin "18") (pinfunction "18_18") (pintype "passive"))
      (node (ref "BAUD") (pin "2") (pinfunction "2_2") (pintype "passive"))
      (node (ref "BAUD") (pin "20") (pinfunction "20_20") (pintype "passive"))
      (node (ref "BAUD") (pin "22") (pinfunction "22_22") (pintype "passive"))
      (node (ref "BAUD") (pin "24") (pinfunction "24_24") (pintype "passive"))
      (node (ref "BAUD") (pin "26") (pinfunction "26_26") (pintype "passive"))
      (node (ref "BAUD") (pin "4") (pinfunction "4_4") (pintype "passive"))
      (node (ref "BAUD") (pin "6") (pinfunction "6_6") (pintype "passive"))
      (node (ref "BAUD") (pin "8") (pinfunction "8_8") (pintype "passive"))
      (node (ref "E1") (pin "23") (pinfunction "IO16_23") (pintype "bidirectional"))
    )
    (net (code "83") (name "unconnected-(ACB1P-Pad19)") (class "Default")
      (node (ref "ACB1P") (pin "19") (pinfunction "19_19") (pintype "passive"))
    )
    (net (code "84") (name "unconnected-(ACB2P-Pad19)") (class "Default")
      (node (ref "ACB2P") (pin "19") (pinfunction "19_19") (pintype "passive"))
    )
    (net (code "85") (name "unconnected-(BAC1P-Pad19)") (class "Default")
      (node (ref "BAC1P") (pin "19") (pinfunction "19_19") (pintype "passive"))
    )
    (net (code "86") (name "unconnected-(BAC2P-Pad19)") (class "Default")
      (node (ref "BAC2P") (pin "19") (pinfunction "19_19") (pintype "passive"))
    )
    (net (code "87") (name "unconnected-(BMB1P-Pad19)") (class "Default")
      (node (ref "BMB1P") (pin "19") (pinfunction "19_19") (pintype "passive"))
    )
    (net (code "88") (name "unconnected-(BMB2P-Pad19)") (class "Default")
      (node (ref "BMB2P") (pin "19") (pinfunction "19_19") (pintype "passive"))
    )
    (net (code "89") (name "unconnected-(DAD1P-Pad19)") (class "Default")
      (node (ref "DAD1P") (pin "19") (pinfunction "19_19") (pintype "passive"))
    )
    (net (code "90") (name "unconnected-(DAD2P-Pad19)") (class "Default")
      (node (ref "DAD2P") (pin "19") (pinfunction "19_19") (pintype "passive"))
    )
    (net (code "91") (name "unconnected-(DAT1P-Pad19)") (class "Default")
      (node (ref "DAT1P") (pin "19") (pinfunction "19_19") (pintype "passive"))
    )
    (net (code "92") (name "unconnected-(DAT2P-Pad19)") (class "Default")
      (node (ref "DAT2P") (pin "19") (pinfunction "19_19") (pintype "passive"))
    )
    (net (code "93") (name "unconnected-(E1Q-IN{slash}OE1-Pad90)") (class "Default")
      (node (ref "E1") (pin "90") (pinfunction "IN/OE1_90") (pintype "input"))
    )
    (net (code "94") (name "unconnected-(E1Q-IO34-Pad46)") (class "Default")
      (node (ref "E1") (pin "46") (pinfunction "IO34_46") (pintype "bidirectional"))
    )
    (net (code "95") (name "unconnected-(E1Q-IO35-Pad47)") (class "Default")
      (node (ref "E1") (pin "47") (pinfunction "IO35_47") (pintype "bidirectional"))
    )
    (net (code "96") (name "unconnected-(E1Q-IO42-Pad55)") (class "Default")
      (node (ref "E1") (pin "55") (pinfunction "IO42_55") (pintype "bidirectional"))
    )
    (net (code "97") (name "unconnected-(E1Q-IO69-Pad94)") (class "Default")
      (node (ref "E1") (pin "94") (pinfunction "IO69_94") (pintype "bidirectional"))
    )
    (net (code "98") (name "unconnected-(E1Q-IO70-Pad95)") (class "Default")
      (node (ref "E1") (pin "95") (pinfunction "IO70_95") (pintype "bidirectional"))
    )
    (net (code "99") (name "unconnected-(E1Q-IO71-Pad96)") (class "Default")
      (node (ref "E1") (pin "96") (pinfunction "IO71_96") (pintype "bidirectional"))
    )
    (net (code "100") (name "unconnected-(E1Q-IO72-Pad98)") (class "Default")
      (node (ref "E1") (pin "98") (pinfunction "IO72_98") (pintype "bidirectional"))
    )
    (net (code "101") (name "unconnected-(E1Q-IO73-Pad99)") (class "Default")
      (node (ref "E1") (pin "99") (pinfunction "IO73_99") (pintype "bidirectional"))
    )
    (net (code "102") (name "unconnected-(E1Q-IO74-Pad100)") (class "Default")
      (node (ref "E1") (pin "100") (pinfunction "IO74_100") (pintype "bidirectional"))
    )
    (net (code "103") (name "unconnected-(E1Q-IO75-Pad1)") (class "Default")
      (node (ref "E1") (pin "1") (pinfunction "IO75_1") (pintype "bidirectional"))
    )
    (net (code "104") (name "unconnected-(E2B-A-Pad4)") (class "Default")
      (node (ref "E2") (pin "4") (pinfunction "A_4") (pintype "passive"))
    )
    (net (code "105") (name "unconnected-(E2B-C-Pad3)") (class "Default")
      (node (ref "E2") (pin "3") (pinfunction "C_3") (pintype "passive"))
    )
    (net (code "106") (name "unconnected-(E2B-COL-Pad14)") (class "Default")
      (node (ref "E2") (pin "14") (pinfunction "COL_14") (pintype "passive"))
    )
    (net (code "107") (name "unconnected-(E3A-R1OUT-Pad12)") (class "Default")
      (node (ref "E3") (pin "12") (pinfunction "R1OUT_12") (pintype "output"))
    )
    (net (code "108") (name "unconnected-(J1-4-PadD)") (class "Default")
      (node (ref "J1") (pin "D") (pinfunction "4_D") (pintype "bidirectional"))
    )
    (net (code "109") (name "unconnected-(J1-10-PadL)") (class "Default")
      (node (ref "J1") (pin "L") (pinfunction "10_L") (pintype "bidirectional"))
    )
    (net (code "110") (name "unconnected-(J1-12-PadN)") (class "Default")
      (node (ref "J1") (pin "N") (pinfunction "12_N") (pintype "bidirectional"))
    )
    (net (code "111") (name "unconnected-(J1-13-PadP)") (class "Default")
      (node (ref "J1") (pin "P") (pinfunction "13_P") (pintype "bidirectional"))
    )
    (net (code "112") (name "unconnected-(J1-14-PadR)") (class "Default")
      (node (ref "J1") (pin "R") (pinfunction "14_R") (pintype "bidirectional"))
    )
    (net (code "113") (name "unconnected-(J1-16-PadT)") (class "Default")
      (node (ref "J1") (pin "T") (pinfunction "16_T") (pintype "bidirectional"))
    )
    (net (code "114") (name "unconnected-(J1-17-PadU)") (class "Default")
      (node (ref "J1") (pin "U") (pinfunction "17_U") (pintype "bidirectional"))
    )
    (net (code "115") (name "unconnected-(J1-19-PadW)") (class "Default")
      (node (ref "J1") (pin "W") (pinfunction "19_W") (pintype "bidirectional"))
    )
    (net (code "116") (name "unconnected-(J1-20-PadX)") (class "Default")
      (node (ref "J1") (pin "X") (pinfunction "20_X") (pintype "bidirectional"))
    )
    (net (code "117") (name "unconnected-(J1-21-PadY)") (class "Default")
      (node (ref "J1") (pin "Y") (pinfunction "21_Y") (pintype "bidirectional"))
    )
    (net (code "118") (name "unconnected-(J1-22-PadZ)") (class "Default")
      (node (ref "J1") (pin "Z") (pinfunction "22_Z") (pintype "bidirectional"))
    )
    (net (code "119") (name "unconnected-(J1-24-PadBB)") (class "Default")
      (node (ref "J1") (pin "BB") (pinfunction "24_BB") (pintype "bidirectional"))
    )
    (net (code "120") (name "unconnected-(J1-25-PadCC)") (class "Default")
      (node (ref "J1") (pin "CC") (pinfunction "25_CC") (pintype "bidirectional"))
    )
    (net (code "121") (name "unconnected-(J1-28-PadFF)") (class "Default")
      (node (ref "J1") (pin "FF") (pinfunction "28_FF") (pintype "bidirectional"))
    )
    (net (code "122") (name "unconnected-(J1-29-PadHH)") (class "Default")
      (node (ref "J1") (pin "HH") (pinfunction "29_HH") (pintype "bidirectional"))
    )
    (net (code "123") (name "unconnected-(J1-30-PadJJ)") (class "Default")
      (node (ref "J1") (pin "JJ") (pinfunction "30_JJ") (pintype "bidirectional"))
    )
    (net (code "124") (name "unconnected-(J1-32-PadLL)") (class "Default")
      (node (ref "J1") (pin "LL") (pinfunction "32_LL") (pintype "bidirectional"))
    )
    (net (code "125") (name "unconnected-(J1-33-PadMM)") (class "Default")
      (node (ref "J1") (pin "MM") (pinfunction "33_MM") (pintype "bidirectional"))
    )
    (net (code "126") (name "unconnected-(J1-34-PadNN)") (class "Default")
      (node (ref "J1") (pin "NN") (pinfunction "34_NN") (pintype "bidirectional"))
    )
    (net (code "127") (name "unconnected-(J1-36-PadRR)") (class "Default")
      (node (ref "J1") (pin "RR") (pinfunction "36_RR") (pintype "bidirectional"))
    )
    (net (code "128") (name "unconnected-(J1-37-PadSS)") (class "Default")
      (node (ref "J1") (pin "SS") (pinfunction "37_SS") (pintype "bidirectional"))
    )
    (net (code "129") (name "unconnected-(J1-38-PadTT)") (class "Default")
      (node (ref "J1") (pin "TT") (pinfunction "38_TT") (pintype "bidirectional"))
    )
    (net (code "130") (name "unconnected-(PROG1-Pad6)") (class "Default")
      (node (ref "PROG1") (pin "6") (pinfunction "6_6") (pintype "passive"))
    )
    (net (code "131") (name "unconnected-(PROG1-Pad7)") (class "Default")
      (node (ref "PROG1") (pin "7") (pinfunction "7_7") (pintype "passive"))
    )
    (net (code "132") (name "unconnected-(PROG1-Pad8)") (class "Default")
      (node (ref "PROG1") (pin "8") (pinfunction "8_8") (pintype "passive"))
    )
    (net (code "133") (name "~{ACLR}") (class "Default")
      (node (ref "ACB2P") (pin "7") (pinfunction "7_7") (pintype "passive"))
      (node (ref "E1") (pin "78") (pinfunction "IO60_78") (pintype "bidirectional"))
    )
    (net (code "134") (name "~{ADDA}") (class "Default")
      (node (ref "DAD2P") (pin "5") (pinfunction "5_5") (pintype "passive"))
    )
    (net (code "135") (name "~{BREAK}") (class "Default")
      (node (ref "DAD2P") (pin "7") (pinfunction "7_7") (pintype "passive"))
    )
    (net (code "136") (name "~{BRQ}") (class "Default")
      (node (ref "DAD2P") (pin "11") (pinfunction "11_11") (pintype "passive"))
    )
    (net (code "137") (name "~{CANCR}") (class "Default")
      (node (ref "DAT2P") (pin "9") (pinfunction "9_9") (pintype "passive"))
    )
    (net (code "138") (name "~{CYC3}") (class "Default")
      (node (ref "DAT2P") (pin "11") (pinfunction "11_11") (pintype "passive"))
    )
    (net (code "139") (name "~{D-IN}") (class "Default")
      (node (ref "DAD2P") (pin "9") (pinfunction "9_9") (pintype "passive"))
    )
    (net (code "140") (name "~{DAD00}") (class "Default")
      (node (ref "DAD1P") (pin "17") (pinfunction "17_17") (pintype "passive"))
    )
    (net (code "141") (name "~{DAD01}") (class "Default")
      (node (ref "DAD1P") (pin "15") (pinfunction "15_15") (pintype "passive"))
    )
    (net (code "142") (name "~{DAD02}") (class "Default")
      (node (ref "DAD1P") (pin "13") (pinfunction "13_13") (pintype "passive"))
    )
    (net (code "143") (name "~{DAD03}") (class "Default")
      (node (ref "DAD1P") (pin "11") (pinfunction "11_11") (pintype "passive"))
    )
    (net (code "144") (name "~{DAD04}") (class "Default")
      (node (ref "DAD1P") (pin "9") (pinfunction "9_9") (pintype "passive"))
    )
    (net (code "145") (name "~{DAD05}") (class "Default")
      (node (ref "DAD1P") (pin "7") (pinfunction "7_7") (pintype "passive"))
    )
    (net (code "146") (name "~{DAD06}") (class "Default")
      (node (ref "DAD1P") (pin "5") (pinfunction "5_5") (pintype "passive"))
    )
    (net (code "147") (name "~{DAD07}") (class "Default")
      (node (ref "DAD1P") (pin "3") (pinfunction "3_3") (pintype "passive"))
    )
    (net (code "148") (name "~{DAD08}") (class "Default")
      (node (ref "DAD1P") (pin "1") (pinfunction "1_1") (pintype "passive"))
    )
    (net (code "149") (name "~{DAD09}") (class "Default")
      (node (ref "DAD2P") (pin "17") (pinfunction "17_17") (pintype "passive"))
    )
    (net (code "150") (name "~{DAD10}") (class "Default")
      (node (ref "DAD2P") (pin "15") (pinfunction "15_15") (pintype "passive"))
    )
    (net (code "151") (name "~{DAD11}") (class "Default")
      (node (ref "DAD2P") (pin "13") (pinfunction "13_13") (pintype "passive"))
    )
    (net (code "152") (name "~{DAT00}") (class "Default")
      (node (ref "DAT1P") (pin "17") (pinfunction "17_17") (pintype "passive"))
    )
    (net (code "153") (name "~{DAT01}") (class "Default")
      (node (ref "DAT1P") (pin "15") (pinfunction "15_15") (pintype "passive"))
    )
    (net (code "154") (name "~{DAT02}") (class "Default")
      (node (ref "DAT1P") (pin "13") (pinfunction "13_13") (pintype "passive"))
    )
    (net (code "155") (name "~{DAT03}") (class "Default")
      (node (ref "DAT1P") (pin "11") (pinfunction "11_11") (pintype "passive"))
    )
    (net (code "156") (name "~{DAT04}") (class "Default")
      (node (ref "DAT1P") (pin "9") (pinfunction "9_9") (pintype "passive"))
    )
    (net (code "157") (name "~{DAT05}") (class "Default")
      (node (ref "DAT1P") (pin "7") (pinfunction "7_7") (pintype "passive"))
    )
    (net (code "158") (name "~{DAT06}") (class "Default")
      (node (ref "DAT1P") (pin "5") (pinfunction "5_5") (pintype "passive"))
    )
    (net (code "159") (name "~{DAT07}") (class "Default")
      (node (ref "DAT1P") (pin "3") (pinfunction "3_3") (pintype "passive"))
    )
    (net (code "160") (name "~{DAT08}") (class "Default")
      (node (ref "DAT1P") (pin "1") (pinfunction "1_1") (pintype "passive"))
    )
    (net (code "161") (name "~{DAT09}") (class "Default")
      (node (ref "DAT2P") (pin "17") (pinfunction "17_17") (pintype "passive"))
    )
    (net (code "162") (name "~{DAT10}") (class "Default")
      (node (ref "DAT2P") (pin "15") (pinfunction "15_15") (pintype "passive"))
    )
    (net (code "163") (name "~{DAT11}") (class "Default")
      (node (ref "DAT2P") (pin "13") (pinfunction "13_13") (pintype "passive"))
    )
    (net (code "164") (name "~{EXDA0}") (class "Default")
      (node (ref "DAT2P") (pin "1") (pinfunction "1_1") (pintype "passive"))
    )
    (net (code "165") (name "~{EXDA1}") (class "Default")
      (node (ref "DAT2P") (pin "3") (pinfunction "3_3") (pintype "passive"))
    )
    (net (code "166") (name "~{EXDA2}") (class "Default")
      (node (ref "DAT2P") (pin "5") (pinfunction "5_5") (pintype "passive"))
    )
    (net (code "167") (name "~{IB00}") (class "Default")
      (node (ref "ACB1P") (pin "17") (pinfunction "17_17") (pintype "passive"))
      (node (ref "E1") (pin "66") (pinfunction "IO51_66") (pintype "bidirectional"))
    )
    (net (code "168") (name "~{IB01}") (class "Default")
      (node (ref "ACB1P") (pin "15") (pinfunction "15_15") (pintype "passive"))
      (node (ref "E1") (pin "69") (pinfunction "IO53_69") (pintype "bidirectional"))
    )
    (net (code "169") (name "~{IB02}") (class "Default")
      (node (ref "ACB1P") (pin "13") (pinfunction "13_13") (pintype "passive"))
      (node (ref "E1") (pin "71") (pinfunction "IO55_71") (pintype "bidirectional"))
    )
    (net (code "170") (name "~{IB03}") (class "Default")
      (node (ref "ACB1P") (pin "11") (pinfunction "11_11") (pintype "passive"))
      (node (ref "E1") (pin "73") (pinfunction "IO57_73") (pintype "bidirectional"))
    )
    (net (code "171") (name "~{IB04}") (class "Default")
      (node (ref "ACB1P") (pin "9") (pinfunction "9_9") (pintype "passive"))
      (node (ref "E1") (pin "77") (pinfunction "IO59_77") (pintype "bidirectional"))
    )
    (net (code "172") (name "~{IB05}") (class "Default")
      (node (ref "ACB1P") (pin "7") (pinfunction "7_7") (pintype "passive"))
      (node (ref "E1") (pin "79") (pinfunction "IO61_79") (pintype "bidirectional"))
    )
    (net (code "173") (name "~{IB06}") (class "Default")
      (node (ref "ACB1P") (pin "5") (pinfunction "5_5") (pintype "passive"))
      (node (ref "E1") (pin "81") (pinfunction "IO63_81") (pintype "bidirectional"))
    )
    (net (code "174") (name "~{IB07}") (class "Default")
      (node (ref "ACB1P") (pin "3") (pinfunction "3_3") (pintype "passive"))
      (node (ref "E1") (pin "83") (pinfunction "IO65_83") (pintype "bidirectional"))
    )
    (net (code "175") (name "~{IB08}") (class "Default")
      (node (ref "ACB1P") (pin "1") (pinfunction "1_1") (pintype "passive"))
      (node (ref "E1") (pin "86") (pinfunction "IO67_86") (pintype "bidirectional"))
    )
    (net (code "176") (name "~{IB09}") (class "Default")
      (node (ref "ACB2P") (pin "17") (pinfunction "17_17") (pintype "passive"))
      (node (ref "E1") (pin "65") (pinfunction "IO50_65") (pintype "bidirectional"))
    )
    (net (code "177") (name "~{IB10}") (class "Default")
      (node (ref "ACB2P") (pin "15") (pinfunction "15_15") (pintype "passive"))
      (node (ref "E1") (pin "67") (pinfunction "IO52_67") (pintype "bidirectional"))
    )
    (net (code "178") (name "~{IB11}") (class "Default")
      (node (ref "ACB2P") (pin "13") (pinfunction "13_13") (pintype "passive"))
      (node (ref "E1") (pin "70") (pinfunction "IO54_70") (pintype "bidirectional"))
    )
    (net (code "179") (name "~{IRQ}") (class "Default")
      (node (ref "ACB2P") (pin "9") (pinfunction "9_9") (pintype "passive"))
      (node (ref "E1") (pin "74") (pinfunction "IO58_74") (pintype "bidirectional"))
    )
    (net (code "180") (name "~{LINE}") (class "Default")
      (node (ref "ACB2P") (pin "1") (pinfunction "1_1") (pintype "passive"))
      (node (ref "E1") (pin "85") (pinfunction "IO66_85") (pintype "bidirectional"))
    )
    (net (code "181") (name "~{MB03}") (class "Default")
      (node (ref "BMB1P") (pin "11") (pinfunction "11_11") (pintype "passive"))
    )
    (net (code "182") (name "~{MB04}") (class "Default")
      (node (ref "BMB1P") (pin "7") (pinfunction "7_7") (pintype "passive"))
    )
    (net (code "183") (name "~{MB05}") (class "Default")
      (node (ref "BMB1P") (pin "3") (pinfunction "3_3") (pintype "passive"))
    )
    (net (code "184") (name "~{MB06}") (class "Default")
      (node (ref "BMB2P") (pin "17") (pinfunction "17_17") (pintype "passive"))
    )
    (net (code "185") (name "~{MB07}") (class "Default")
      (node (ref "BMB2P") (pin "13") (pinfunction "13_13") (pintype "passive"))
    )
    (net (code "186") (name "~{MB08}") (class "Default")
      (node (ref "BMB2P") (pin "9") (pinfunction "9_9") (pintype "passive"))
    )
    (net (code "187") (name "~{MNCR}") (class "Default")
      (node (ref "DAD2P") (pin "3") (pinfunction "3_3") (pintype "passive"))
    )
    (net (code "188") (name "~{RUN}") (class "Default")
      (node (ref "ACB2P") (pin "5") (pinfunction "5_5") (pintype "passive"))
      (node (ref "E1") (pin "80") (pinfunction "IO62_80") (pintype "bidirectional"))
    )
    (net (code "189") (name "~{SKIP}") (class "Default")
      (node (ref "ACB2P") (pin "11") (pinfunction "11_11") (pintype "passive"))
      (node (ref "E1") (pin "72") (pinfunction "IO56_72") (pintype "bidirectional"))
    )
    (net (code "190") (name "~{TTINST}") (class "Default")
      (node (ref "ACB2P") (pin "3") (pinfunction "3_3") (pintype "passive"))
      (node (ref "E1") (pin "82") (pinfunction "IO64_82") (pintype "bidirectional"))
    )
    (net (code "191") (name "~{WCOVF}") (class "Default")
      (node (ref "DAT2P") (pin "7") (pinfunction "7_7") (pintype "passive"))
    )
  )
)
